# MOTORES-L293D.net
KiCad netlist of a schematic drawn in EAGLE
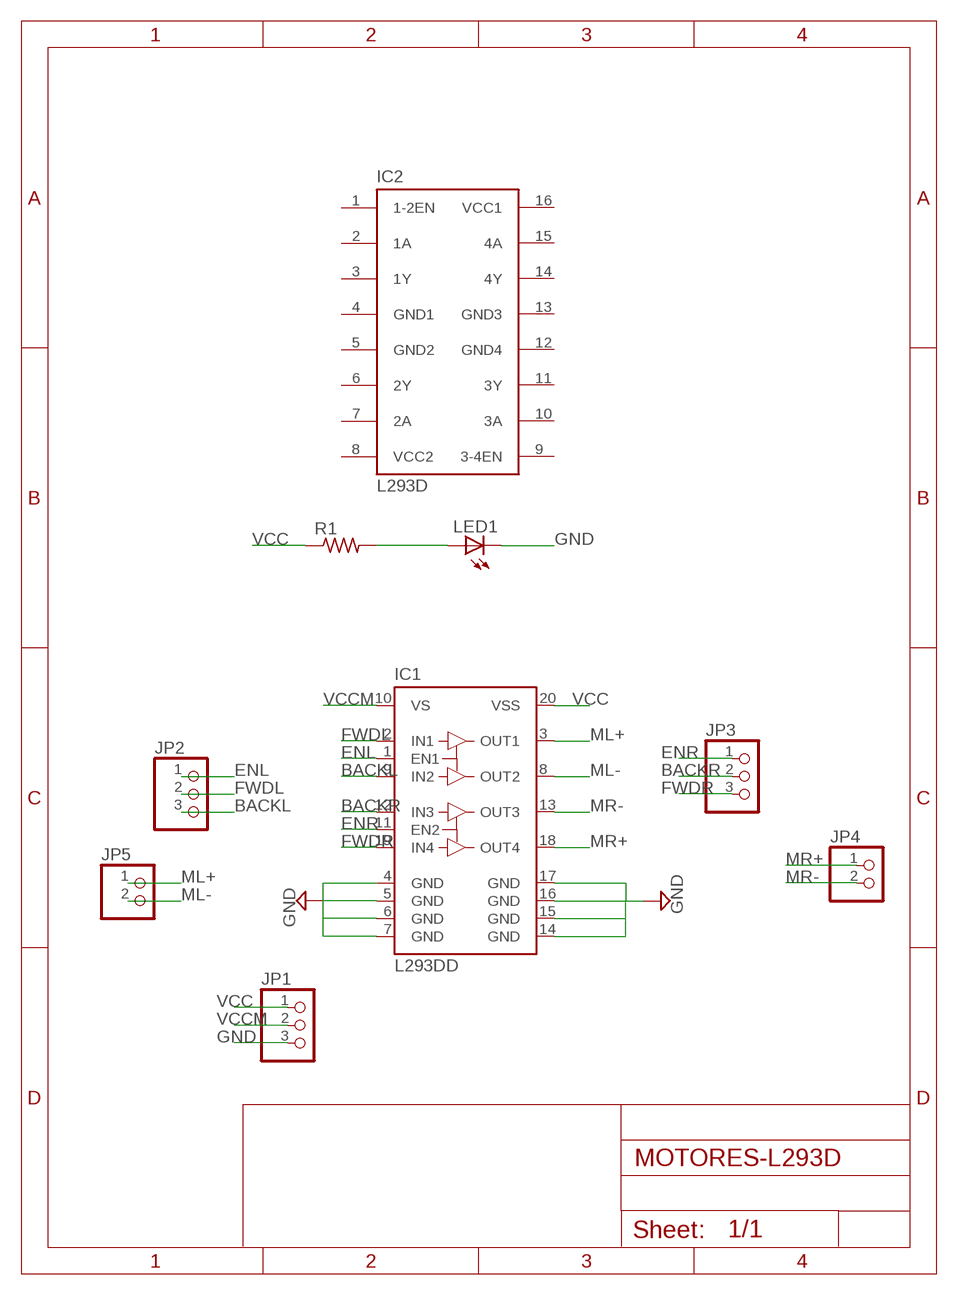
[diagram p0: schematic, sheet 1]

(export (version "E")
  (design (tool "Eeschema 10.0.6"))
  (components
    (comp (ref "IC1")
      (value "L293DD")
      (footprint "eagle-import:SO20")
      (libsource (lib "eagle-import") (part "L293DD"))
    )
    (comp (ref "IC2")
      (value "L293D")
      (footprint "eagle-import:DIL16")
      (libsource (lib "eagle-import") (part "L293D"))
    )
    (comp (ref "JP1")
      (value "PINHD-1X3")
      (footprint "eagle-import:1X03")
      (libsource (lib "eagle-import") (part "PINHD-1X3"))
    )
    (comp (ref "JP2")
      (value "PINHD-1X3")
      (footprint "eagle-import:1X03")
      (libsource (lib "eagle-import") (part "PINHD-1X3"))
    )
    (comp (ref "JP3")
      (value "PINHD-1X3")
      (footprint "eagle-import:1X03")
      (libsource (lib "eagle-import") (part "PINHD-1X3"))
    )
    (comp (ref "JP4")
      (value "PINHD-1X2")
      (footprint "eagle-import:1X02")
      (libsource (lib "eagle-import") (part "PINHD-1X2"))
    )
    (comp (ref "JP5")
      (value "PINHD-1X2")
      (footprint "eagle-import:1X02")
      (libsource (lib "eagle-import") (part "PINHD-1X2"))
    )
    (comp (ref "LED1")
      (value "LED5MM")
      (footprint "eagle-import:LED5MM")
      (libsource (lib "eagle-import") (part "LED5MM"))
    )
    (comp (ref "R1")
      (value "R-US_R0603")
      (footprint "eagle-import:R0603")
      (libsource (lib "eagle-import") (part "R-US_R0603"))
    )
  )
  (nets
    (net (code "1") (name "/BACKL") (class "Default")
      (node (ref "IC1") (pin "9") (pinfunction "IN2_9") (pintype "input"))
      (node (ref "JP2") (pin "3") (pinfunction "3_3") (pintype "passive"))
    )
    (net (code "2") (name "/BACKR") (class "Default")
      (node (ref "IC1") (pin "12") (pinfunction "IN3_12") (pintype "input"))
      (node (ref "JP3") (pin "2") (pinfunction "2_2") (pintype "passive"))
    )
    (net (code "3") (name "/ENL") (class "Default")
      (node (ref "IC1") (pin "1") (pinfunction "EN1_1") (pintype "input"))
      (node (ref "JP2") (pin "1") (pinfunction "1_1") (pintype "passive"))
    )
    (net (code "4") (name "/ENR") (class "Default")
      (node (ref "IC1") (pin "11") (pinfunction "EN2_11") (pintype "input"))
      (node (ref "JP3") (pin "1") (pinfunction "1_1") (pintype "passive"))
    )
    (net (code "5") (name "/FWDL") (class "Default")
      (node (ref "IC1") (pin "2") (pinfunction "IN1_2") (pintype "input"))
      (node (ref "JP2") (pin "2") (pinfunction "2_2") (pintype "passive"))
    )
    (net (code "6") (name "/FWDR") (class "Default")
      (node (ref "IC1") (pin "19") (pinfunction "IN4_19") (pintype "input"))
      (node (ref "JP3") (pin "3") (pinfunction "3_3") (pintype "passive"))
    )
    (net (code "7") (name "/GND1") (class "Default")
      (node (ref "IC2") (pin "4") (pinfunction "GND1_4") (pintype "power_in"))
    )
    (net (code "8") (name "/GND2") (class "Default")
      (node (ref "IC2") (pin "5") (pinfunction "GND2_5") (pintype "power_in"))
    )
    (net (code "9") (name "/GND3") (class "Default")
      (node (ref "IC2") (pin "13") (pinfunction "GND3_13") (pintype "power_in"))
    )
    (net (code "10") (name "/GND4") (class "Default")
      (node (ref "IC2") (pin "12") (pinfunction "GND4_12") (pintype "power_in"))
    )
    (net (code "11") (name "/ML+") (class "Default")
      (node (ref "IC1") (pin "3") (pinfunction "OUT1_3") (pintype "output"))
      (node (ref "JP5") (pin "1") (pinfunction "1_1") (pintype "passive"))
    )
    (net (code "12") (name "/ML-") (class "Default")
      (node (ref "IC1") (pin "8") (pinfunction "OUT2_8") (pintype "output"))
      (node (ref "JP5") (pin "2") (pinfunction "2_2") (pintype "passive"))
    )
    (net (code "13") (name "/MR+") (class "Default")
      (node (ref "IC1") (pin "18") (pinfunction "OUT4_18") (pintype "output"))
      (node (ref "JP4") (pin "1") (pinfunction "1_1") (pintype "passive"))
    )
    (net (code "14") (name "/MR-") (class "Default")
      (node (ref "IC1") (pin "13") (pinfunction "OUT3_13") (pintype "output"))
      (node (ref "JP4") (pin "2") (pinfunction "2_2") (pintype "passive"))
    )
    (net (code "15") (name "/VCC") (class "Default")
      (node (ref "IC1") (pin "20") (pinfunction "VSS_20") (pintype "power_in"))
      (node (ref "JP1") (pin "1") (pinfunction "1_1") (pintype "passive"))
      (node (ref "R1") (pin "1") (pinfunction "1_1") (pintype "passive"))
    )
    (net (code "16") (name "/VCC1") (class "Default")
      (node (ref "IC2") (pin "16") (pinfunction "VCC1_16") (pintype "power_in"))
    )
    (net (code "17") (name "/VCC2") (class "Default")
      (node (ref "IC2") (pin "8") (pinfunction "VCC2_8") (pintype "power_in"))
    )
    (net (code "18") (name "/VCCM") (class "Default")
      (node (ref "IC1") (pin "10") (pinfunction "VS_10") (pintype "power_in"))
      (node (ref "JP1") (pin "2") (pinfunction "2_2") (pintype "passive"))
    )
    (net (code "19") (name "GND") (class "Default")
      (node (ref "IC1") (pin "14") (pinfunction "GND_14") (pintype "power_in"))
      (node (ref "IC1") (pin "15") (pinfunction "GND_15") (pintype "power_in"))
      (node (ref "IC1") (pin "16") (pinfunction "GND_16") (pintype "power_in"))
      (node (ref "IC1") (pin "17") (pinfunction "GND_17") (pintype "power_in"))
      (node (ref "IC1") (pin "4") (pinfunction "GND_4") (pintype "power_in"))
      (node (ref "IC1") (pin "5") (pinfunction "GND_5") (pintype "power_in"))
      (node (ref "IC1") (pin "6") (pinfunction "GND_6") (pintype "power_in"))
      (node (ref "IC1") (pin "7") (pinfunction "GND_7") (pintype "power_in"))
      (node (ref "JP1") (pin "3") (pinfunction "3_3") (pintype "passive"))
      (node (ref "LED1") (pin "K") (pinfunction "C_K") (pintype "passive"))
    )
    (net (code "20") (name "Net-(LED1-PadA)") (class "Default")
      (node (ref "LED1") (pin "A") (pinfunction "A_A") (pintype "passive"))
      (node (ref "R1") (pin "2") (pinfunction "2_2") (pintype "passive"))
    )
    (net (code "21") (name "unconnected-(IC2-1-2EN-Pad1)") (class "Default")
      (node (ref "IC2") (pin "1") (pinfunction "1-2EN_1") (pintype "input"))
    )
    (net (code "22") (name "unconnected-(IC2-1A-Pad2)") (class "Default")
      (node (ref "IC2") (pin "2") (pinfunction "1A_2") (pintype "input"))
    )
    (net (code "23") (name "unconnected-(IC2-1Y-Pad3)") (class "Default")
      (node (ref "IC2") (pin "3") (pinfunction "1Y_3") (pintype "output"))
    )
    (net (code "24") (name "unconnected-(IC2-2A-Pad7)") (class "Default")
      (node (ref "IC2") (pin "7") (pinfunction "2A_7") (pintype "input"))
    )
    (net (code "25") (name "unconnected-(IC2-2Y-Pad6)") (class "Default")
      (node (ref "IC2") (pin "6") (pinfunction "2Y_6") (pintype "output"))
    )
    (net (code "26") (name "unconnected-(IC2-3-4EN-Pad9)") (class "Default")
      (node (ref "IC2") (pin "9") (pinfunction "3-4EN_9") (pintype "input"))
    )
    (net (code "27") (name "unconnected-(IC2-3A-Pad10)") (class "Default")
      (node (ref "IC2") (pin "10") (pinfunction "3A_10") (pintype "input"))
    )
    (net (code "28") (name "unconnected-(IC2-3Y-Pad11)") (class "Default")
      (node (ref "IC2") (pin "11") (pinfunction "3Y_11") (pintype "output"))
    )
    (net (code "29") (name "unconnected-(IC2-4A-Pad15)") (class "Default")
      (node (ref "IC2") (pin "15") (pinfunction "4A_15") (pintype "input"))
    )
    (net (code "30") (name "unconnected-(IC2-4Y-Pad14)") (class "Default")
      (node (ref "IC2") (pin "14") (pinfunction "4Y_14") (pintype "output"))
    )
  )
)
